# CH32V002A4M.net
KiCad netlist of a schematic drawn in Altium Designer
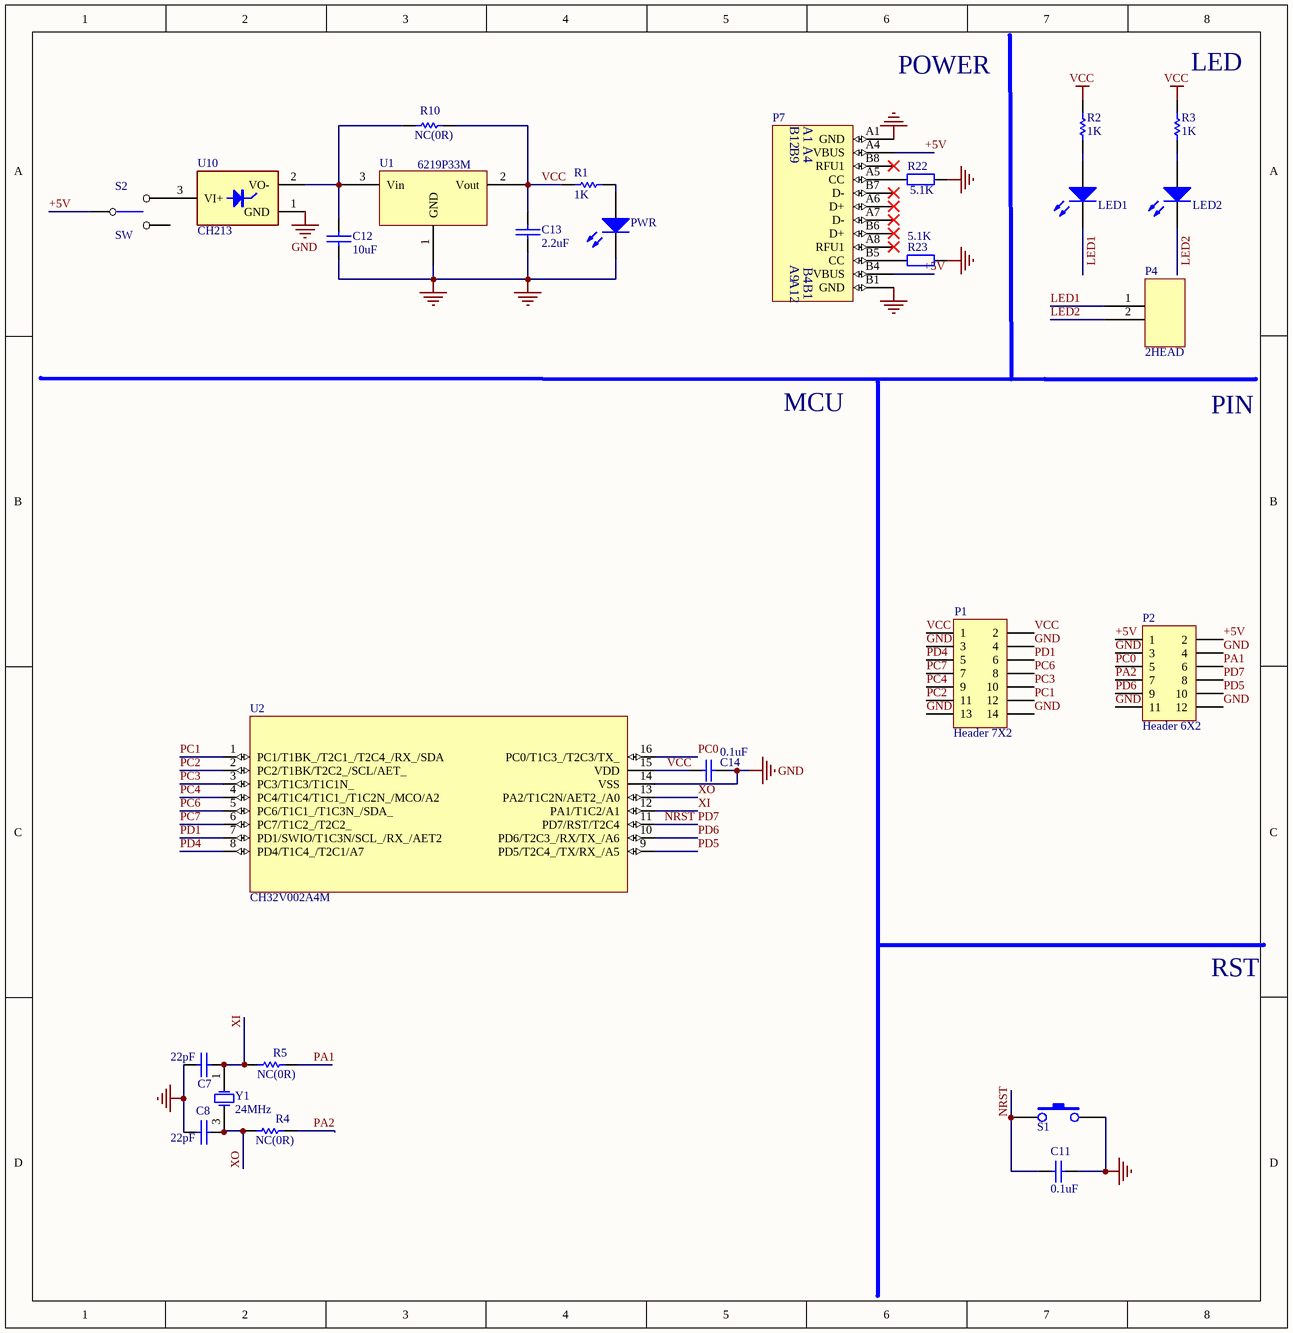
[diagram p0: CH32V002A4M.SchDoc]

(export (version "E")
  (design (tool "Eeschema 10.0.6"))
  (components
    (comp (ref "C7")
      (value "22pF")
      (footprint "0402_C")
      (description "Capacitor")
      (libsource (lib "*") (part "CAP"))
    )
    (comp (ref "C8")
      (value "22pF")
      (footprint "0402_C")
      (description "Capacitor")
      (libsource (lib "*") (part "CAP"))
    )
    (comp (ref "C11")
      (value "0.1uF")
      (footprint "0402_C")
      (description "Capacitor")
      (fields (field (name "PUBLISHER") "Altium Limited"))
      (libsource (lib "*") (part "Cap"))
    )
    (comp (ref "C12")
      (value "10uF")
      (footprint "0603_C")
      (description "Capacitor")
      (libsource (lib "wch_sch_others") (part "CAP"))
    )
    (comp (ref "C13")
      (value "2.2uF")
      (footprint "0402_C")
      (description "Capacitor")
      (libsource (lib "wch_sch_others") (part "CAP"))
    )
    (comp (ref "C14")
      (value "0.1uF")
      (footprint "0603_C")
      (description "Capacitor")
      (fields (field (name "PUBLISHER") "Altium Limited"))
      (libsource (lib "*") (part "Cap"))
    )
    (comp (ref "LED1")
      (value "LED1   blue")
      (footprint "0603+")
      (description "Typical INFRARED GaAs LED")
      (fields (field (name "PUBLISHER") "Altium Limited"))
      (libsource (lib "") (part "LED0_1"))
    )
    (comp (ref "LED2")
      (value "LED2  blue")
      (footprint "0603+")
      (description "Typical INFRARED GaAs LED")
      (fields (field (name "PUBLISHER") "Altium Limited"))
      (libsource (lib "") (part "LED0_1"))
    )
    (comp (ref "P1")
      (value "Header 7X2")
      (footprint "HDR2X7")
      (description "Header, 7-Pin, Dual row")
      (fields (field (name "PUBLISHER") "Altium Limited"))
      (libsource (lib "Miscellaneous Connectors") (part "Header 7X2"))
    )
    (comp (ref "P2")
      (value "Header 6X2")
      (footprint "HDR2X6")
      (description "Header, 6-Pin, Dual row")
      (fields (field (name "PUBLISHER") "Altium Limited"))
      (libsource (lib "Miscellaneous Connectors") (part "Header 6X2"))
    )
    (comp (ref "P4") (value "2HEAD") (footprint "SIP2-2.54mm") (libsource (lib "*") (part "2HEAD")))
    (comp (ref "P7")
      (value "TYPE-C")
      (footprint "TYPE-C-Receptacle-2.0")
      (libsource (lib "*") (part "TYPE-C1"))
    )
    (comp (ref "PWR")
      (value "POWER  red")
      (footprint "0603+")
      (description "Typical INFRARED GaAs LED")
      (fields (field (name "PUBLISHER") "Altium Limited"))
      (libsource (lib "*") (part "LED0"))
    )
    (comp (ref "R1")
      (value "1K")
      (footprint "0402")
      (description "Semiconductor Resistor")
      (fields (field (name "PUBLISHER") "Altium Limited"))
      (libsource (lib "*") (part "Res Semi"))
    )
    (comp (ref "R2")
      (value "1K")
      (footprint "0402")
      (description "Semiconductor Resistor")
      (fields (field (name "PUBLISHER") "Altium Limited"))
      (libsource (lib "*") (part "Res Semi"))
    )
    (comp (ref "R3")
      (value "1K")
      (footprint "0402")
      (description "Semiconductor Resistor")
      (fields (field (name "PUBLISHER") "Altium Limited"))
      (libsource (lib "*") (part "Res Semi"))
    )
    (comp (ref "R4")
      (value "NC(0R)")
      (footprint "0402")
      (description "Semiconductor Resistor")
      (fields (field (name "Comment") "0R") (field (name "PUBLISHER") "Altium Limited"))
      (libsource (lib "*") (part "Res Semi"))
    )
    (comp (ref "R5")
      (value "NC(0R)")
      (footprint "0402")
      (description "Semiconductor Resistor")
      (fields (field (name "Comment") "0R") (field (name "PUBLISHER") "Altium Limited"))
      (libsource (lib "*") (part "Res Semi"))
    )
    (comp (ref "R10")
      (value "NC(0R)")
      (footprint "0402")
      (description "Semiconductor Resistor")
      (fields (field (name "Comment") "0R") (field (name "PUBLISHER") "Altium Limited"))
      (libsource (lib "*") (part "Res Semi"))
    )
    (comp (ref "R22")
      (value "5.1K")
      (footprint "0402")
      (description "Resistor")
      (libsource (lib "Miscellaneous Devices") (part "Res2"))
    )
    (comp (ref "R23")
      (value "5.1K")
      (footprint "0402")
      (description "Resistor")
      (libsource (lib "Miscellaneous Devices") (part "Res2"))
    )
    (comp (ref "S1") (value "NRST") (footprint "SMD_6.1x3.65x2.5mm-KEY") (libsource (lib "*") (part "KEY")))
    (comp (ref "S2") (value "SW") (footprint "SW1") (libsource (lib "*") (part "SW")))
    (comp (ref "U1")
      (value "6219P33M")
      (footprint "SOT-23")
      (libsource (lib "wch_sch_others") (part "6219P33M"))
    )
    (comp (ref "U2")
      (value "CH32V002A4M")
      (footprint "SOP16")
      (description "RISC-V MCU, 48MHz, ADC/UART/I2C")
      (libsource (lib "DHXXXSCH") (part "CH32V002A4M6"))
    )
    (comp (ref "U10")
      (value "CH213")
      (footprint "SOT-23-3")
      (description "Ideal Diode 5V*1A")
      (libsource (lib "CHXXX") (part "CH213E"))
    )
    (comp (ref "Y1")
      (value "24MHz")
      (footprint "XT3225")
      (description "Crystal Oscillator")
      (fields (field (name "PUBLISHER") "Altium Limited"))
      (libsource (lib "*") (part "XTAL"))
    )
  )
  (nets
    (net (code "1") (name "/+5V") (class "Default")
      (node (ref "P2") (pin "1") (pinfunction "1_1") (pintype "passive"))
      (node (ref "P2") (pin "2") (pinfunction "2_2") (pintype "passive"))
      (node (ref "P7") (pin "A4") (pinfunction "VBUS_A4") (pintype "bidirectional"))
      (node (ref "P7") (pin "B4") (pinfunction "VBUS_B4") (pintype "bidirectional"))
      (node (ref "S2") (pin "1") (pinfunction "1_1") (pintype "passive"))
    )
    (net (code "2") (name "/LED1") (class "Default")
      (node (ref "LED1") (pin "2") (pinfunction "K_2") (pintype "passive"))
      (node (ref "P4") (pin "1") (pintype "passive"))
    )
    (net (code "3") (name "/LED2") (class "Default")
      (node (ref "LED2") (pin "2") (pinfunction "K_2") (pintype "passive"))
      (node (ref "P4") (pin "2") (pintype "passive"))
    )
    (net (code "4") (name "/NRST") (class "Default")
      (node (ref "C11") (pin "2") (pinfunction "2_2") (pintype "passive"))
      (node (ref "P2") (pin "8") (pinfunction "8_8") (pintype "passive"))
      (node (ref "S1") (pin "1") (pinfunction "1_1") (pintype "passive"))
      (node (ref "U2") (pin "11") (pinfunction "PD7/RST/T2C4_11") (pintype "bidirectional"))
    )
    (net (code "5") (name "/PA1") (class "Default")
      (node (ref "P2") (pin "6") (pinfunction "6_6") (pintype "passive"))
      (node (ref "R5") (pin "2") (pinfunction "2_2") (pintype "passive"))
    )
    (net (code "6") (name "/PA2") (class "Default")
      (node (ref "P2") (pin "7") (pinfunction "7_7") (pintype "passive"))
      (node (ref "R4") (pin "2") (pinfunction "2_2") (pintype "passive"))
    )
    (net (code "7") (name "/PC0") (class "Default")
      (node (ref "P2") (pin "5") (pinfunction "5_5") (pintype "passive"))
      (node (ref "U2") (pin "16") (pinfunction "PC0/T1C3_/T2C3/TX__16") (pintype "bidirectional"))
    )
    (net (code "8") (name "/PC1") (class "Default")
      (node (ref "P1") (pin "12") (pinfunction "12_12") (pintype "passive"))
      (node (ref "U2") (pin "1") (pinfunction "PC1/T1BK_/T2C1_/T2C4_/RX_/SDA_1") (pintype "bidirectional"))
    )
    (net (code "9") (name "/PC2") (class "Default")
      (node (ref "P1") (pin "11") (pinfunction "11_11") (pintype "passive"))
      (node (ref "U2") (pin "2") (pinfunction "PC2/T1BK/T2C2_/SCL/AET__2") (pintype "bidirectional"))
    )
    (net (code "10") (name "/PC3") (class "Default")
      (node (ref "P1") (pin "10") (pinfunction "10_10") (pintype "passive"))
      (node (ref "U2") (pin "3") (pinfunction "PC3/T1C3/T1C1N__3") (pintype "bidirectional"))
    )
    (net (code "11") (name "/PC4") (class "Default")
      (node (ref "P1") (pin "9") (pinfunction "9_9") (pintype "passive"))
      (node (ref "U2") (pin "4") (pinfunction "PC4/T1C4/T1C1_/T1C2N_/MCO/A2_4") (pintype "bidirectional"))
    )
    (net (code "12") (name "/PC6") (class "Default")
      (node (ref "P1") (pin "8") (pinfunction "8_8") (pintype "passive"))
      (node (ref "U2") (pin "5") (pinfunction "PC6/T1C1_/T1C3N_/SDA__5") (pintype "bidirectional"))
    )
    (net (code "13") (name "/PC7") (class "Default")
      (node (ref "P1") (pin "7") (pinfunction "7_7") (pintype "passive"))
      (node (ref "U2") (pin "6") (pinfunction "PC7/T1C2_/T2C2__6") (pintype "bidirectional"))
    )
    (net (code "14") (name "/PD1") (class "Default")
      (node (ref "P1") (pin "6") (pinfunction "6_6") (pintype "passive"))
      (node (ref "U2") (pin "7") (pinfunction "PD1/SWIO/T1C3N/SCL_/RX_/AET2_7") (pintype "bidirectional"))
    )
    (net (code "15") (name "/PD4") (class "Default")
      (node (ref "P1") (pin "5") (pinfunction "5_5") (pintype "passive"))
      (node (ref "U2") (pin "8") (pinfunction "PD4/T1C4_/T2C1/A7_8") (pintype "bidirectional"))
    )
    (net (code "16") (name "/PD5") (class "Default")
      (node (ref "P2") (pin "10") (pinfunction "10_10") (pintype "passive"))
      (node (ref "U2") (pin "9") (pinfunction "PD5/T2C4_/TX/RX_/A5_9") (pintype "bidirectional"))
    )
    (net (code "17") (name "/PD6") (class "Default")
      (node (ref "P2") (pin "9") (pinfunction "9_9") (pintype "passive"))
      (node (ref "U2") (pin "10") (pinfunction "PD6/T2C3_/RX/TX_/A6_10") (pintype "bidirectional"))
    )
    (net (code "18") (name "/XI") (class "Default")
      (node (ref "C7") (pin "2") (pinfunction "2_2") (pintype "passive"))
      (node (ref "R5") (pin "1") (pinfunction "1_1") (pintype "passive"))
      (node (ref "U2") (pin "12") (pinfunction "PA1/T1C2/A1_12") (pintype "bidirectional"))
      (node (ref "Y1") (pin "1") (pinfunction "OSC1_1") (pintype "passive"))
    )
    (net (code "19") (name "/XO") (class "Default")
      (node (ref "C8") (pin "2") (pinfunction "2_2") (pintype "passive"))
      (node (ref "R4") (pin "1") (pinfunction "1_1") (pintype "passive"))
      (node (ref "U2") (pin "13") (pinfunction "PA2/T1C2N/AET2_/A0_13") (pintype "bidirectional"))
      (node (ref "Y1") (pin "3") (pinfunction "OSC2_3") (pintype "passive"))
    )
    (net (code "20") (name "GND") (class "Default")
      (node (ref "C11") (pin "1") (pinfunction "1_1") (pintype "passive"))
      (node (ref "C12") (pin "2") (pinfunction "2_2") (pintype "passive"))
      (node (ref "C13") (pin "1") (pinfunction "1_1") (pintype "passive"))
      (node (ref "C14") (pin "2") (pinfunction "2_2") (pintype "passive"))
      (node (ref "C7") (pin "1") (pinfunction "1_1") (pintype "passive"))
      (node (ref "C8") (pin "1") (pinfunction "1_1") (pintype "passive"))
      (node (ref "P1") (pin "13") (pinfunction "13_13") (pintype "passive"))
      (node (ref "P1") (pin "14") (pinfunction "14_14") (pintype "passive"))
      (node (ref "P1") (pin "3") (pinfunction "3_3") (pintype "passive"))
      (node (ref "P1") (pin "4") (pinfunction "4_4") (pintype "passive"))
      (node (ref "P2") (pin "11") (pinfunction "11_11") (pintype "passive"))
      (node (ref "P2") (pin "12") (pinfunction "12_12") (pintype "passive"))
      (node (ref "P2") (pin "3") (pinfunction "3_3") (pintype "passive"))
      (node (ref "P2") (pin "4") (pinfunction "4_4") (pintype "passive"))
      (node (ref "P7") (pin "A1") (pinfunction "GND_A1") (pintype "bidirectional"))
      (node (ref "P7") (pin "B1") (pinfunction "GND_B1") (pintype "bidirectional"))
      (node (ref "PWR") (pin "2") (pinfunction "K_2") (pintype "passive"))
      (node (ref "R22") (pin "2") (pinfunction "2_2") (pintype "passive"))
      (node (ref "R23") (pin "2") (pinfunction "2_2") (pintype "passive"))
      (node (ref "S1") (pin "2") (pinfunction "2_2") (pintype "passive"))
      (node (ref "U1") (pin "1") (pinfunction "GND_1") (pintype "passive"))
      (node (ref "U10") (pin "1") (pinfunction "GND_1") (pintype "power_in"))
      (node (ref "U2") (pin "14") (pinfunction "VSS_14") (pintype "power_in"))
    )
    (net (code "21") (name "Net-(LED1-A)") (class "Default")
      (node (ref "LED1") (pin "1") (pinfunction "A_1") (pintype "passive"))
      (node (ref "R2") (pin "2") (pinfunction "2_2") (pintype "passive"))
    )
    (net (code "22") (name "Net-(LED2-A)") (class "Default")
      (node (ref "LED2") (pin "1") (pinfunction "A_1") (pintype "passive"))
      (node (ref "R3") (pin "2") (pinfunction "2_2") (pintype "passive"))
    )
    (net (code "23") (name "Net-(P7-CC-PadA5)") (class "Default")
      (node (ref "P7") (pin "A5") (pinfunction "CC_A5") (pintype "bidirectional"))
      (node (ref "R22") (pin "1") (pinfunction "1_1") (pintype "passive"))
    )
    (net (code "24") (name "Net-(P7-CC-PadB5)") (class "Default")
      (node (ref "P7") (pin "B5") (pinfunction "CC_B5") (pintype "bidirectional"))
      (node (ref "R23") (pin "1") (pinfunction "1_1") (pintype "passive"))
    )
    (net (code "25") (name "Net-(PWR-A)") (class "Default")
      (node (ref "PWR") (pin "1") (pinfunction "A_1") (pintype "passive"))
      (node (ref "R1") (pin "1") (pinfunction "1_1") (pintype "passive"))
    )
    (net (code "26") (name "Net-(U1-Vin)") (class "Default")
      (node (ref "C12") (pin "1") (pinfunction "1_1") (pintype "passive"))
      (node (ref "R10") (pin "1") (pinfunction "1_1") (pintype "passive"))
      (node (ref "U1") (pin "3") (pinfunction "Vin_3") (pintype "passive"))
      (node (ref "U10") (pin "2") (pinfunction "VO-_2") (pintype "power_in"))
    )
    (net (code "27") (name "Net-(U10-VI+)") (class "Default")
      (node (ref "S2") (pin "3") (pinfunction "3_3") (pintype "passive"))
      (node (ref "U10") (pin "3") (pinfunction "VI+_3") (pintype "power_in"))
    )
    (net (code "28") (name "VCC") (class "Default")
      (node (ref "C13") (pin "2") (pinfunction "2_2") (pintype "passive"))
      (node (ref "C14") (pin "1") (pinfunction "1_1") (pintype "passive"))
      (node (ref "P1") (pin "1") (pinfunction "1_1") (pintype "passive"))
      (node (ref "P1") (pin "2") (pinfunction "2_2") (pintype "passive"))
      (node (ref "R1") (pin "2") (pinfunction "2_2") (pintype "passive"))
      (node (ref "R10") (pin "2") (pinfunction "2_2") (pintype "passive"))
      (node (ref "R2") (pin "1") (pinfunction "1_1") (pintype "passive"))
      (node (ref "R3") (pin "1") (pinfunction "1_1") (pintype "passive"))
      (node (ref "U1") (pin "2") (pinfunction "Vout_2") (pintype "passive"))
      (node (ref "U2") (pin "15") (pinfunction "VDD_15") (pintype "power_in"))
    )
    (net (code "29") (name "unconnected-(P7-D+-PadA6)") (class "Default")
      (node (ref "P7") (pin "A6") (pinfunction "D+_A6") (pintype "bidirectional+no_connect"))
    )
    (net (code "30") (name "unconnected-(P7-D+-PadB6)") (class "Default")
      (node (ref "P7") (pin "B6") (pinfunction "D+_B6") (pintype "bidirectional+no_connect"))
    )
    (net (code "31") (name "unconnected-(P7-D--PadA7)") (class "Default")
      (node (ref "P7") (pin "A7") (pinfunction "D-_A7") (pintype "bidirectional+no_connect"))
    )
    (net (code "32") (name "unconnected-(P7-D--PadB7)") (class "Default")
      (node (ref "P7") (pin "B7") (pinfunction "D-_B7") (pintype "bidirectional+no_connect"))
    )
    (net (code "33") (name "unconnected-(P7-RFU1-PadA8)") (class "Default")
      (node (ref "P7") (pin "A8") (pinfunction "RFU1_A8") (pintype "bidirectional+no_connect"))
    )
    (net (code "34") (name "unconnected-(P7-RFU1-PadB8)") (class "Default")
      (node (ref "P7") (pin "B8") (pinfunction "RFU1_B8") (pintype "bidirectional+no_connect"))
    )
    (net (code "35") (name "unconnected-(S2-Pad2)") (class "Default")
      (node (ref "S2") (pin "2") (pinfunction "2_2") (pintype "passive"))
    )
  )
)
